# PMOD-RS485TX.net
KiCad netlist of a schematic drawn in EAGLE
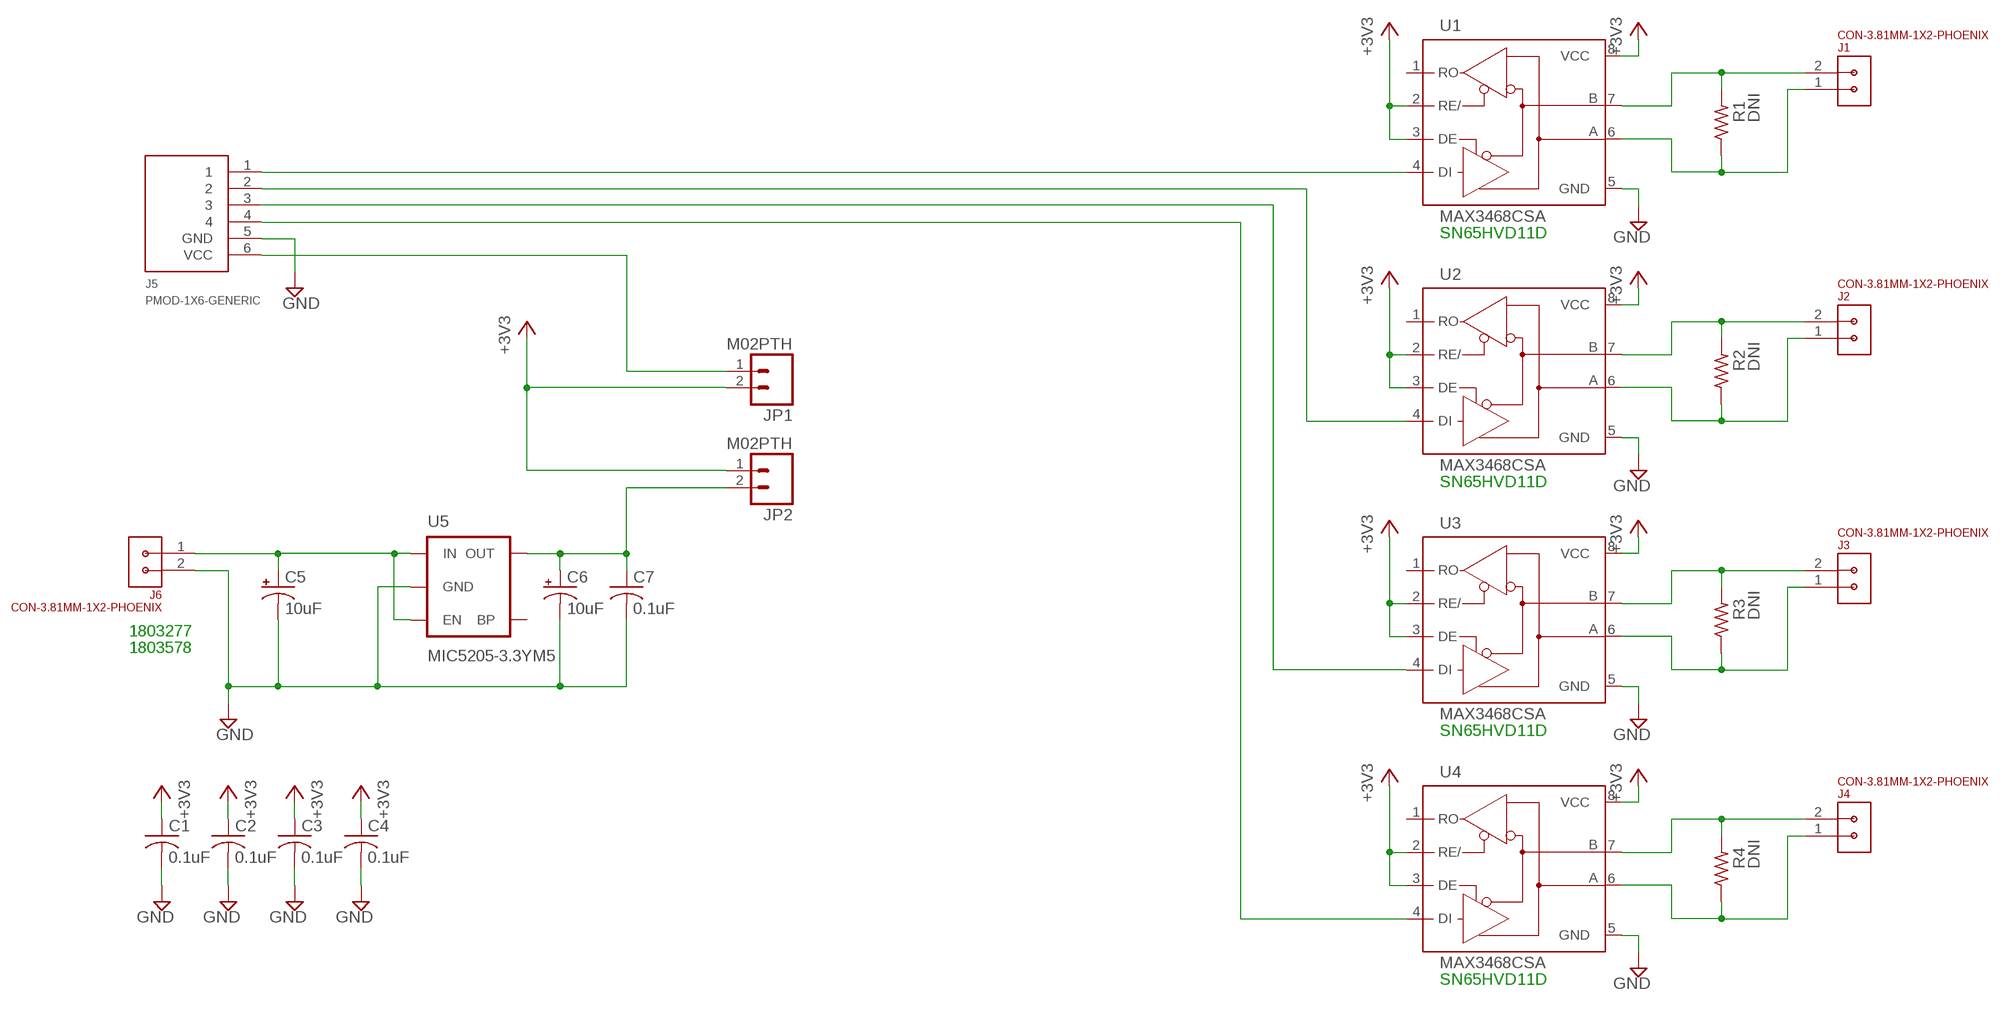
[diagram p0: schematic, sheet 1]

(export (version "E")
  (design (tool "Eeschema 10.0.6"))
  (components
    (comp (ref "C1")
      (value "0.1uF")
      (footprint "eagle-import:C1206")
      (libsource (lib "eagle-import") (part "C-USC1206"))
    )
    (comp (ref "C2")
      (value "0.1uF")
      (footprint "eagle-import:C1206")
      (libsource (lib "eagle-import") (part "C-USC1206"))
    )
    (comp (ref "C3")
      (value "0.1uF")
      (footprint "eagle-import:C1206")
      (libsource (lib "eagle-import") (part "C-USC1206"))
    )
    (comp (ref "C4")
      (value "0.1uF")
      (footprint "eagle-import:C1206")
      (libsource (lib "eagle-import") (part "C-USC1206"))
    )
    (comp (ref "C5")
      (value "10uF")
      (footprint "eagle-import:PANASONIC_D")
      (libsource (lib "eagle-import") (part "CPOL-USD"))
    )
    (comp (ref "C6")
      (value "10uF")
      (footprint "eagle-import:PANASONIC_D")
      (libsource (lib "eagle-import") (part "CPOL-USD"))
    )
    (comp (ref "C7")
      (value "0.1uF")
      (footprint "eagle-import:C1206")
      (libsource (lib "eagle-import") (part "C-USC1206"))
    )
    (comp (ref "J1")
      (value "CON-3.81MM-1X2-PHOENIX")
      (footprint "eagle-import:CON-PHOENIX-3.81-1X2-RA")
      (libsource (lib "eagle-import") (part "CON-3.81MM-1X2-PHOENIX"))
    )
    (comp (ref "J2")
      (value "CON-3.81MM-1X2-PHOENIX")
      (footprint "eagle-import:CON-PHOENIX-3.81-1X2-RA")
      (libsource (lib "eagle-import") (part "CON-3.81MM-1X2-PHOENIX"))
    )
    (comp (ref "J3")
      (value "CON-3.81MM-1X2-PHOENIX")
      (footprint "eagle-import:CON-PHOENIX-3.81-1X2-RA")
      (libsource (lib "eagle-import") (part "CON-3.81MM-1X2-PHOENIX"))
    )
    (comp (ref "J4")
      (value "CON-3.81MM-1X2-PHOENIX")
      (footprint "eagle-import:CON-PHOENIX-3.81-1X2-RA")
      (libsource (lib "eagle-import") (part "CON-3.81MM-1X2-PHOENIX"))
    )
    (comp (ref "J5")
      (value "PMOD-1X6-GENERIC")
      (footprint "eagle-import:CON-PMOD-1X6")
      (libsource (lib "eagle-import") (part "PMOD-1X6-GENERIC"))
    )
    (comp (ref "J6")
      (value "CON-3.81MM-1X2-PHOENIX")
      (footprint "eagle-import:CON-PHOENIX-3.81-1X2-RA")
      (libsource (lib "eagle-import") (part "CON-3.81MM-1X2-PHOENIX"))
    )
    (comp (ref "JP1")
      (value "M02PTH")
      (footprint "eagle-import:1X02")
      (libsource (lib "eagle-import") (part "M02PTH"))
    )
    (comp (ref "JP2")
      (value "M02PTH")
      (footprint "eagle-import:1X02")
      (libsource (lib "eagle-import") (part "M02PTH"))
    )
    (comp (ref "R1")
      (value "DNI")
      (footprint "eagle-import:M1206")
      (libsource (lib "eagle-import") (part "R-US_M1206"))
    )
    (comp (ref "R2")
      (value "DNI")
      (footprint "eagle-import:M1206")
      (libsource (lib "eagle-import") (part "R-US_M1206"))
    )
    (comp (ref "R3")
      (value "DNI")
      (footprint "eagle-import:M1206")
      (libsource (lib "eagle-import") (part "R-US_M1206"))
    )
    (comp (ref "R4")
      (value "DNI")
      (footprint "eagle-import:M1206")
      (libsource (lib "eagle-import") (part "R-US_M1206"))
    )
    (comp (ref "U1")
      (value "MAX3468CSA")
      (footprint "eagle-import:SO08")
      (fields (field (name "MPN") "MAX3468CSA+"))
      (libsource (lib "eagle-import") (part "MAX34SA68C"))
    )
    (comp (ref "U2")
      (value "MAX3468CSA")
      (footprint "eagle-import:SO08")
      (fields (field (name "MPN") "MAX3468CSA+"))
      (libsource (lib "eagle-import") (part "MAX34SA68C"))
    )
    (comp (ref "U3")
      (value "MAX3468CSA")
      (footprint "eagle-import:SO08")
      (fields (field (name "MPN") "MAX3468CSA+"))
      (libsource (lib "eagle-import") (part "MAX34SA68C"))
    )
    (comp (ref "U4")
      (value "MAX3468CSA")
      (footprint "eagle-import:SO08")
      (fields (field (name "MPN") "MAX3468CSA+"))
      (libsource (lib "eagle-import") (part "MAX34SA68C"))
    )
    (comp (ref "U5")
      (value "MIC5205-3.3YM5")
      (footprint "eagle-import:SOT23-5")
      (libsource (lib "eagle-import") (part "V_REG_LDOSMD"))
    )
  )
  (nets
    (net (code "1") (name "+3V3") (class "Default")
      (node (ref "C1") (pin "1") (pinfunction "1_1") (pintype "passive"))
      (node (ref "C2") (pin "1") (pinfunction "1_1") (pintype "passive"))
      (node (ref "C3") (pin "1") (pinfunction "1_1") (pintype "passive"))
      (node (ref "C4") (pin "1") (pinfunction "1_1") (pintype "passive"))
      (node (ref "JP1") (pin "2") (pinfunction "2_2") (pintype "passive"))
      (node (ref "JP2") (pin "1") (pinfunction "1_1") (pintype "passive"))
      (node (ref "U1") (pin "2") (pinfunction "RE/_2") (pintype "input"))
      (node (ref "U1") (pin "3") (pinfunction "DE_3") (pintype "input"))
      (node (ref "U1") (pin "8") (pinfunction "VCC_8") (pintype "power_in"))
      (node (ref "U2") (pin "2") (pinfunction "RE/_2") (pintype "input"))
      (node (ref "U2") (pin "3") (pinfunction "DE_3") (pintype "input"))
      (node (ref "U2") (pin "8") (pinfunction "VCC_8") (pintype "power_in"))
      (node (ref "U3") (pin "2") (pinfunction "RE/_2") (pintype "input"))
      (node (ref "U3") (pin "3") (pinfunction "DE_3") (pintype "input"))
      (node (ref "U3") (pin "8") (pinfunction "VCC_8") (pintype "power_in"))
      (node (ref "U4") (pin "2") (pinfunction "RE/_2") (pintype "input"))
      (node (ref "U4") (pin "3") (pinfunction "DE_3") (pintype "input"))
      (node (ref "U4") (pin "8") (pinfunction "VCC_8") (pintype "power_in"))
    )
    (net (code "2") (name "GND") (class "Default")
      (node (ref "C1") (pin "2") (pinfunction "2_2") (pintype "passive"))
      (node (ref "C2") (pin "2") (pinfunction "2_2") (pintype "passive"))
      (node (ref "C3") (pin "2") (pinfunction "2_2") (pintype "passive"))
      (node (ref "C4") (pin "2") (pinfunction "2_2") (pintype "passive"))
      (node (ref "C5") (pin "-") (pinfunction "-_-") (pintype "passive"))
      (node (ref "C6") (pin "-") (pinfunction "-_-") (pintype "passive"))
      (node (ref "C7") (pin "2") (pinfunction "2_2") (pintype "passive"))
      (node (ref "J5") (pin "5") (pinfunction "GND_5") (pintype "power_in"))
      (node (ref "J6") (pin "2") (pinfunction "2_2") (pintype "bidirectional"))
      (node (ref "U1") (pin "5") (pinfunction "GND_5") (pintype "power_in"))
      (node (ref "U2") (pin "5") (pinfunction "GND_5") (pintype "power_in"))
      (node (ref "U3") (pin "5") (pinfunction "GND_5") (pintype "power_in"))
      (node (ref "U4") (pin "5") (pinfunction "GND_5") (pintype "power_in"))
      (node (ref "U5") (pin "2") (pinfunction "GND_2") (pintype "input"))
    )
    (net (code "3") (name "Net-(J5-VCC)") (class "Default")
      (node (ref "J5") (pin "6") (pinfunction "VCC_6") (pintype "bidirectional"))
      (node (ref "JP1") (pin "1") (pinfunction "1_1") (pintype "passive"))
    )
    (net (code "4") (name "Net-(U1-A)") (class "Default")
      (node (ref "J1") (pin "1") (pinfunction "1_1") (pintype "bidirectional"))
      (node (ref "R1") (pin "1") (pinfunction "1_1") (pintype "passive"))
      (node (ref "U1") (pin "6") (pinfunction "A_6") (pintype "passive"))
    )
    (net (code "5") (name "Net-(U1-B)") (class "Default")
      (node (ref "J1") (pin "2") (pinfunction "2_2") (pintype "bidirectional"))
      (node (ref "R1") (pin "2") (pinfunction "2_2") (pintype "passive"))
      (node (ref "U1") (pin "7") (pinfunction "B_7") (pintype "passive"))
    )
    (net (code "6") (name "Net-(U1-DI)") (class "Default")
      (node (ref "J5") (pin "1") (pinfunction "1_1") (pintype "bidirectional"))
      (node (ref "U1") (pin "4") (pinfunction "DI_4") (pintype "input"))
    )
    (net (code "7") (name "Net-(U2-A)") (class "Default")
      (node (ref "J2") (pin "1") (pinfunction "1_1") (pintype "bidirectional"))
      (node (ref "R2") (pin "1") (pinfunction "1_1") (pintype "passive"))
      (node (ref "U2") (pin "6") (pinfunction "A_6") (pintype "passive"))
    )
    (net (code "8") (name "Net-(U2-B)") (class "Default")
      (node (ref "J2") (pin "2") (pinfunction "2_2") (pintype "bidirectional"))
      (node (ref "R2") (pin "2") (pinfunction "2_2") (pintype "passive"))
      (node (ref "U2") (pin "7") (pinfunction "B_7") (pintype "passive"))
    )
    (net (code "9") (name "Net-(U2-DI)") (class "Default")
      (node (ref "J5") (pin "2") (pinfunction "2_2") (pintype "bidirectional"))
      (node (ref "U2") (pin "4") (pinfunction "DI_4") (pintype "input"))
    )
    (net (code "10") (name "Net-(U3-A)") (class "Default")
      (node (ref "J3") (pin "1") (pinfunction "1_1") (pintype "bidirectional"))
      (node (ref "R3") (pin "1") (pinfunction "1_1") (pintype "passive"))
      (node (ref "U3") (pin "6") (pinfunction "A_6") (pintype "passive"))
    )
    (net (code "11") (name "Net-(U3-B)") (class "Default")
      (node (ref "J3") (pin "2") (pinfunction "2_2") (pintype "bidirectional"))
      (node (ref "R3") (pin "2") (pinfunction "2_2") (pintype "passive"))
      (node (ref "U3") (pin "7") (pinfunction "B_7") (pintype "passive"))
    )
    (net (code "12") (name "Net-(U3-DI)") (class "Default")
      (node (ref "J5") (pin "3") (pinfunction "3_3") (pintype "bidirectional"))
      (node (ref "U3") (pin "4") (pinfunction "DI_4") (pintype "input"))
    )
    (net (code "13") (name "Net-(U4-A)") (class "Default")
      (node (ref "J4") (pin "1") (pinfunction "1_1") (pintype "bidirectional"))
      (node (ref "R4") (pin "1") (pinfunction "1_1") (pintype "passive"))
      (node (ref "U4") (pin "6") (pinfunction "A_6") (pintype "passive"))
    )
    (net (code "14") (name "Net-(U4-B)") (class "Default")
      (node (ref "J4") (pin "2") (pinfunction "2_2") (pintype "bidirectional"))
      (node (ref "R4") (pin "2") (pinfunction "2_2") (pintype "passive"))
      (node (ref "U4") (pin "7") (pinfunction "B_7") (pintype "passive"))
    )
    (net (code "15") (name "Net-(U4-DI)") (class "Default")
      (node (ref "J5") (pin "4") (pinfunction "4_4") (pintype "bidirectional"))
      (node (ref "U4") (pin "4") (pinfunction "DI_4") (pintype "input"))
    )
    (net (code "16") (name "Net-(U5-EN)") (class "Default")
      (node (ref "C5") (pin "+") (pinfunction "+_+") (pintype "passive"))
      (node (ref "J6") (pin "1") (pinfunction "1_1") (pintype "bidirectional"))
      (node (ref "U5") (pin "1") (pinfunction "IN_1") (pintype "input"))
      (node (ref "U5") (pin "3") (pinfunction "EN_3") (pintype "input"))
    )
    (net (code "17") (name "Net-(U5-OUT)") (class "Default")
      (node (ref "C6") (pin "+") (pinfunction "+_+") (pintype "passive"))
      (node (ref "C7") (pin "1") (pinfunction "1_1") (pintype "passive"))
      (node (ref "JP2") (pin "2") (pinfunction "2_2") (pintype "passive"))
      (node (ref "U5") (pin "5") (pinfunction "OUT_5") (pintype "passive"))
    )
    (net (code "18") (name "unconnected-(U1-RO-Pad1)") (class "Default")
      (node (ref "U1") (pin "1") (pinfunction "RO_1") (pintype "output"))
    )
    (net (code "19") (name "unconnected-(U2-RO-Pad1)") (class "Default")
      (node (ref "U2") (pin "1") (pinfunction "RO_1") (pintype "output"))
    )
    (net (code "20") (name "unconnected-(U3-RO-Pad1)") (class "Default")
      (node (ref "U3") (pin "1") (pinfunction "RO_1") (pintype "output"))
    )
    (net (code "21") (name "unconnected-(U4-RO-Pad1)") (class "Default")
      (node (ref "U4") (pin "1") (pinfunction "RO_1") (pintype "output"))
    )
    (net (code "22") (name "unconnected-(U5-BP-Pad4)") (class "Default")
      (node (ref "U5") (pin "4") (pinfunction "BP_4") (pintype "input"))
    )
  )
)
